# main.net
KiCad netlist of a schematic drawn in EAGLE
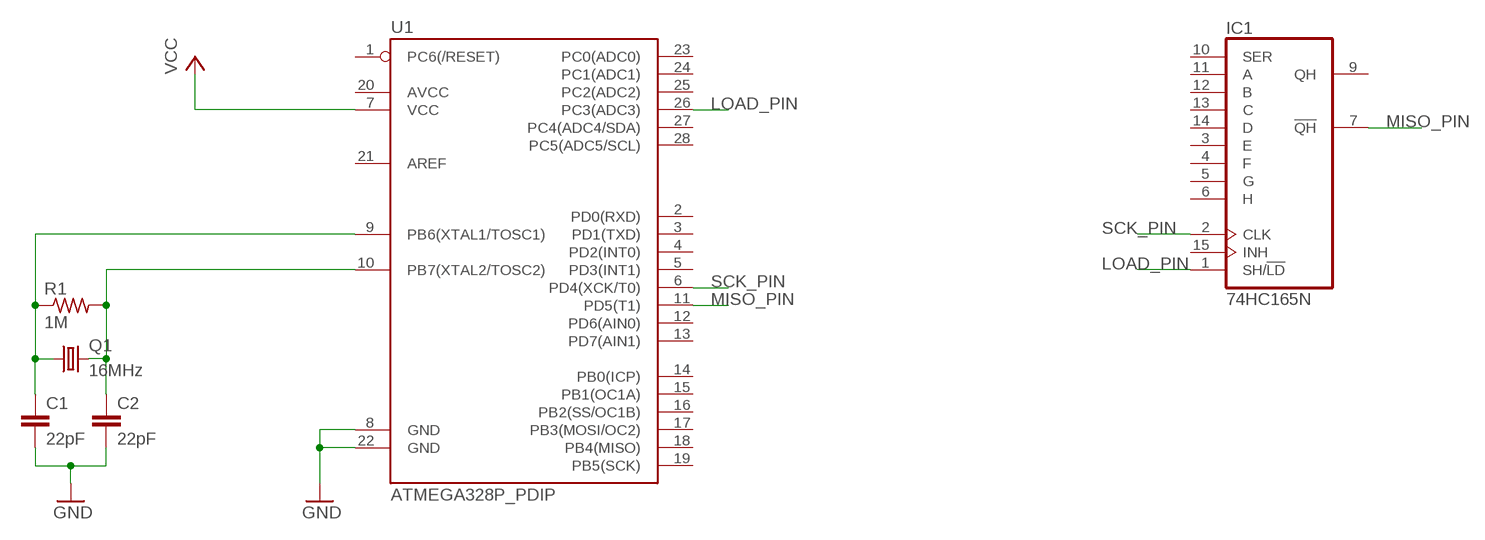
[diagram p0: schematic, sheet 1]

(export (version "E")
  (design (tool "Eeschema 10.0.6"))
  (components
    (comp (ref "C1")
      (value "22pF")
      (footprint "eagle-import:CAP-PTH-LARGE")
      (libsource (lib "eagle-import") (part "CAPPTH3"))
    )
    (comp (ref "C2")
      (value "22pF")
      (footprint "eagle-import:CAP-PTH-5MM")
      (libsource (lib "eagle-import") (part "CAPPTH1"))
    )
    (comp (ref "IC1")
      (value "74HC165N")
      (footprint "eagle-import:DIL16")
      (libsource (lib "eagle-import") (part "74165NHC"))
    )
    (comp (ref "Q1")
      (value "16MHz")
      (footprint "eagle-import:HC33U-V")
      (libsource (lib "eagle-import") (part "CRYSTALHC33U-V"))
    )
    (comp (ref "R1")
      (value "1M")
      (footprint "eagle-import:0207_10")
      (libsource (lib "eagle-import") (part "R-US_0207/10"))
    )
    (comp (ref "U1")
      (value "ATMEGA328P_PDIP")
      (footprint "eagle-import:DIL28-3")
      (libsource (lib "eagle-import") (part "ATMEGA328P_PDIP"))
    )
  )
  (nets
    (net (code "1") (name "/LOAD_PIN") (class "Default")
      (node (ref "IC1") (pin "1") (pinfunction "SH/~{LD}_1") (pintype "input"))
      (node (ref "U1") (pin "26") (pinfunction "PC3(ADC3)_26") (pintype "bidirectional"))
    )
    (net (code "2") (name "/MISO_PIN") (class "Default")
      (node (ref "IC1") (pin "7") (pinfunction "~{QH}_7") (pintype "output"))
      (node (ref "U1") (pin "11") (pinfunction "PD5(T1)_11") (pintype "bidirectional"))
    )
    (net (code "3") (name "/SCK_PIN") (class "Default")
      (node (ref "IC1") (pin "2") (pinfunction "CLK_2") (pintype "input"))
      (node (ref "U1") (pin "6") (pinfunction "PD4(XCK/T0)_6") (pintype "bidirectional"))
    )
    (net (code "4") (name "GND") (class "Default")
      (node (ref "C1") (pin "2") (pinfunction "2_2") (pintype "passive"))
      (node (ref "C2") (pin "2") (pinfunction "2_2") (pintype "passive"))
      (node (ref "U1") (pin "22") (pinfunction "GND_22") (pintype "bidirectional"))
      (node (ref "U1") (pin "8") (pinfunction "GND_8") (pintype "bidirectional"))
    )
    (net (code "5") (name "Net-(U1-PB6(XTAL1{slash}TOSC1))") (class "Default")
      (node (ref "C1") (pin "1") (pinfunction "1_1") (pintype "passive"))
      (node (ref "Q1") (pin "1") (pinfunction "1_1") (pintype "passive"))
      (node (ref "R1") (pin "1") (pinfunction "1_1") (pintype "passive"))
      (node (ref "U1") (pin "9") (pinfunction "PB6(XTAL1/TOSC1)_9") (pintype "bidirectional"))
    )
    (net (code "6") (name "Net-(U1-PB7(XTAL2{slash}TOSC2))") (class "Default")
      (node (ref "C2") (pin "1") (pinfunction "1_1") (pintype "passive"))
      (node (ref "Q1") (pin "2") (pinfunction "2_2") (pintype "passive"))
      (node (ref "R1") (pin "2") (pinfunction "2_2") (pintype "passive"))
      (node (ref "U1") (pin "10") (pinfunction "PB7(XTAL2/TOSC2)_10") (pintype "bidirectional"))
    )
    (net (code "7") (name "VCC") (class "Default")
      (node (ref "U1") (pin "7") (pinfunction "VCC_7") (pintype "bidirectional"))
    )
    (net (code "8") (name "unconnected-(IC1A-A-Pad11)") (class "Default")
      (node (ref "IC1") (pin "11") (pinfunction "A_11") (pintype "input"))
    )
    (net (code "9") (name "unconnected-(IC1A-B-Pad12)") (class "Default")
      (node (ref "IC1") (pin "12") (pinfunction "B_12") (pintype "input"))
    )
    (net (code "10") (name "unconnected-(IC1A-C-Pad13)") (class "Default")
      (node (ref "IC1") (pin "13") (pinfunction "C_13") (pintype "input"))
    )
    (net (code "11") (name "unconnected-(IC1A-D-Pad14)") (class "Default")
      (node (ref "IC1") (pin "14") (pinfunction "D_14") (pintype "input"))
    )
    (net (code "12") (name "unconnected-(IC1A-E-Pad3)") (class "Default")
      (node (ref "IC1") (pin "3") (pinfunction "E_3") (pintype "input"))
    )
    (net (code "13") (name "unconnected-(IC1A-F-Pad4)") (class "Default")
      (node (ref "IC1") (pin "4") (pinfunction "F_4") (pintype "input"))
    )
    (net (code "14") (name "unconnected-(IC1A-G-Pad5)") (class "Default")
      (node (ref "IC1") (pin "5") (pinfunction "G_5") (pintype "input"))
    )
    (net (code "15") (name "unconnected-(IC1A-H-Pad6)") (class "Default")
      (node (ref "IC1") (pin "6") (pinfunction "H_6") (pintype "input"))
    )
    (net (code "16") (name "unconnected-(IC1A-INH-Pad15)") (class "Default")
      (node (ref "IC1") (pin "15") (pinfunction "INH_15") (pintype "input"))
    )
    (net (code "17") (name "unconnected-(IC1A-QH-Pad9)") (class "Default")
      (node (ref "IC1") (pin "9") (pinfunction "QH_9") (pintype "output"))
    )
    (net (code "18") (name "unconnected-(IC1A-SER-Pad10)") (class "Default")
      (node (ref "IC1") (pin "10") (pinfunction "SER_10") (pintype "input"))
    )
    (net (code "19") (name "unconnected-(U1-AREF-Pad21)") (class "Default")
      (node (ref "U1") (pin "21") (pinfunction "AREF_21") (pintype "bidirectional"))
    )
    (net (code "20") (name "unconnected-(U1-AVCC-Pad20)") (class "Default")
      (node (ref "U1") (pin "20") (pinfunction "AVCC_20") (pintype "bidirectional"))
    )
    (net (code "21") (name "unconnected-(U1-PB0(ICP)-Pad14)") (class "Default")
      (node (ref "U1") (pin "14") (pinfunction "PB0(ICP)_14") (pintype "bidirectional"))
    )
    (net (code "22") (name "unconnected-(U1-PB1(OC1A)-Pad15)") (class "Default")
      (node (ref "U1") (pin "15") (pinfunction "PB1(OC1A)_15") (pintype "bidirectional"))
    )
    (net (code "23") (name "unconnected-(U1-PB2(SS{slash}OC1B)-Pad16)") (class "Default")
      (node (ref "U1") (pin "16") (pinfunction "PB2(SS/OC1B)_16") (pintype "bidirectional"))
    )
    (net (code "24") (name "unconnected-(U1-PB3(MOSI{slash}OC2)-Pad17)") (class "Default")
      (node (ref "U1") (pin "17") (pinfunction "PB3(MOSI/OC2)_17") (pintype "bidirectional"))
    )
    (net (code "25") (name "unconnected-(U1-PB4(MISO)-Pad18)") (class "Default")
      (node (ref "U1") (pin "18") (pinfunction "PB4(MISO)_18") (pintype "bidirectional"))
    )
    (net (code "26") (name "unconnected-(U1-PB5(SCK)-Pad19)") (class "Default")
      (node (ref "U1") (pin "19") (pinfunction "PB5(SCK)_19") (pintype "bidirectional"))
    )
    (net (code "27") (name "unconnected-(U1-PC0(ADC0)-Pad23)") (class "Default")
      (node (ref "U1") (pin "23") (pinfunction "PC0(ADC0)_23") (pintype "bidirectional"))
    )
    (net (code "28") (name "unconnected-(U1-PC1(ADC1)-Pad24)") (class "Default")
      (node (ref "U1") (pin "24") (pinfunction "PC1(ADC1)_24") (pintype "bidirectional"))
    )
    (net (code "29") (name "unconnected-(U1-PC2(ADC2)-Pad25)") (class "Default")
      (node (ref "U1") (pin "25") (pinfunction "PC2(ADC2)_25") (pintype "bidirectional"))
    )
    (net (code "30") (name "unconnected-(U1-PC4(ADC4{slash}SDA)-Pad27)") (class "Default")
      (node (ref "U1") (pin "27") (pinfunction "PC4(ADC4/SDA)_27") (pintype "bidirectional"))
    )
    (net (code "31") (name "unconnected-(U1-PC5(ADC5{slash}SCL)-Pad28)") (class "Default")
      (node (ref "U1") (pin "28") (pinfunction "PC5(ADC5/SCL)_28") (pintype "bidirectional"))
    )
    (net (code "32") (name "unconnected-(U1-PC6({slash}RESET)-Pad1)") (class "Default")
      (node (ref "U1") (pin "1") (pinfunction "PC6(/RESET)_1") (pintype "bidirectional"))
    )
    (net (code "33") (name "unconnected-(U1-PD0(RXD)-Pad2)") (class "Default")
      (node (ref "U1") (pin "2") (pinfunction "PD0(RXD)_2") (pintype "bidirectional"))
    )
    (net (code "34") (name "unconnected-(U1-PD1(TXD)-Pad3)") (class "Default")
      (node (ref "U1") (pin "3") (pinfunction "PD1(TXD)_3") (pintype "bidirectional"))
    )
    (net (code "35") (name "unconnected-(U1-PD2(INT0)-Pad4)") (class "Default")
      (node (ref "U1") (pin "4") (pinfunction "PD2(INT0)_4") (pintype "bidirectional"))
    )
    (net (code "36") (name "unconnected-(U1-PD3(INT1)-Pad5)") (class "Default")
      (node (ref "U1") (pin "5") (pinfunction "PD3(INT1)_5") (pintype "bidirectional"))
    )
    (net (code "37") (name "unconnected-(U1-PD6(AIN0)-Pad12)") (class "Default")
      (node (ref "U1") (pin "12") (pinfunction "PD6(AIN0)_12") (pintype "bidirectional"))
    )
    (net (code "38") (name "unconnected-(U1-PD7(AIN1)-Pad13)") (class "Default")
      (node (ref "U1") (pin "13") (pinfunction "PD7(AIN1)_13") (pintype "bidirectional"))
    )
  )
)
